# ChargerSwitch.net
KiCad netlist of a schematic drawn in Altium Designer
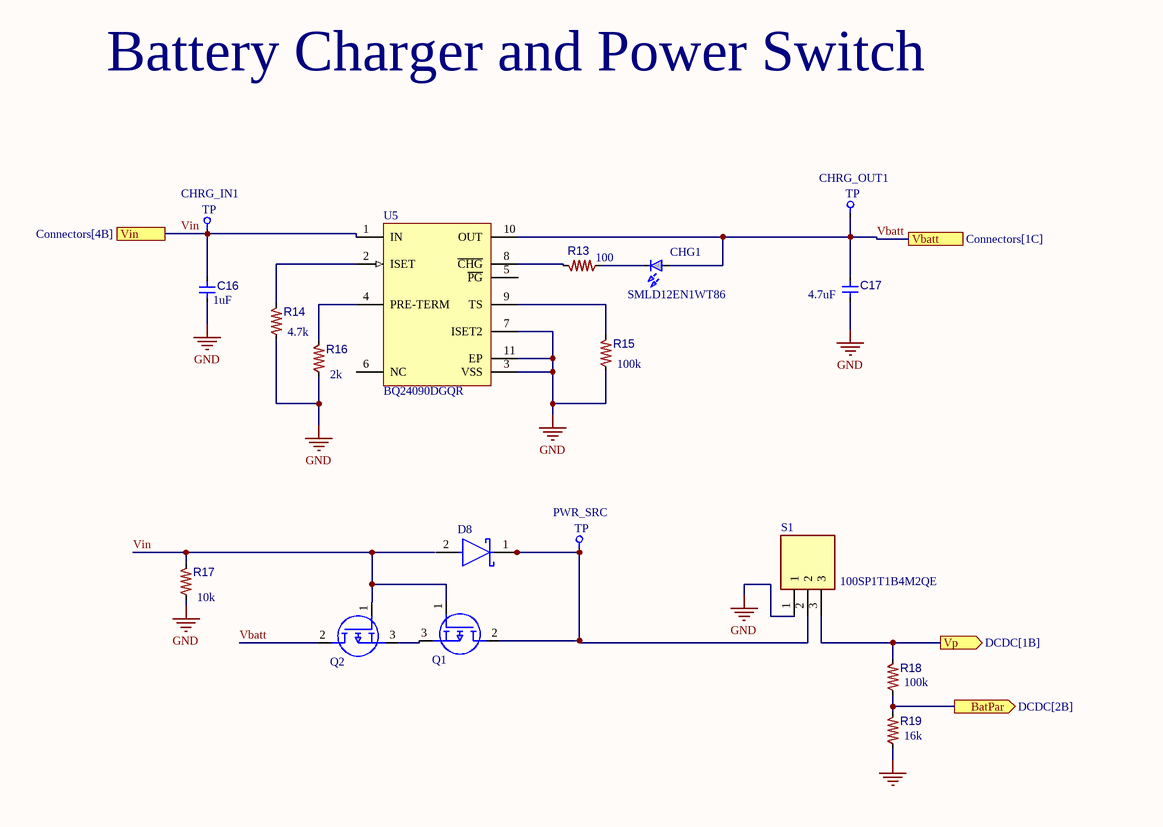
[diagram p0: ChargerSwitch.SchDoc]

(export (version "E")
  (design (tool "Eeschema 10.0.6"))
  (components
    (comp (ref "C16")
      (value "C309479")
      (footprint "New footprint 1")
      (description "6.3V 1uF X7R ±10% 0603  Multilayer Ceramic Capacitors MLCC - SMD/SMT ROHS")
      (libsource (lib "Muner") (part "CAP-NP-2"))
    )
    (comp (ref "C17")
      (value "C77045")
      (footprint "New footprint 1")
      (description "116V 4.7uF X5R ±10% 0603 Multilayer Ceramic Capacitors MLCC - SMD/SMT ROHS")
      (libsource (lib "Muner") (part "CAP-NP-2"))
    )
    (comp (ref "CHG1")
      (value "SMLD12EN1WT86")
      (footprint "LEDM168X65N")
      (description "Standard LEDs - SMD 1.6X0.8MM LOW CRNT")
      (fields (field (name "MOUSER PART NUMBER") "755-SMLD12EN1WT86"))
      (libsource (lib "Muner") (part "CMP-004-00037-6"))
    )
    (comp (ref "CHRG_IN1")
      (value "Test Pad")
      (footprint "Test Pad-Footprint-1")
      (libsource (lib "Muner") (part "Test Pad-Symbol-1"))
    )
    (comp (ref "CHRG_OUT1")
      (value "Test Pad")
      (footprint "Test Pad-Footprint-1")
      (libsource (lib "Muner") (part "Test Pad-Symbol-1"))
    )
    (comp (ref "D8")
      (value "C191986")
      (footprint "FP-MBR1020VL_R1_00001-MFG")
      (description "20V 340mV@1A 1A SOD-123F  Schottky Barrier Diodes (SBD) ROHS")
      (libsource (lib "Altium Content Vault") (part "c1678fac7984e62e0809fbf79c06691"))
    )
    (comp (ref "PWR_SRC")
      (value "Test Pad")
      (footprint "Test Pad-Footprint-1")
      (libsource (lib "Muner") (part "Test Pad-Symbol-1"))
    )
    (comp (ref "Q1")
      (value "C113491")
      (footprint "TSM260P02CXRFG")
      (description "20V 6.5A 1.4W 27mΩ@4.5V,6.5A N Channel SOT-23(TO-236)  MOSFETs ROHS")
      (fields
        (field (name "MANUFACTURER_PART_NUMBER") "TSM260P02CX RFG")
        (field (name "MOUSER PART NUMBER") "821-TSM260P02CXRFG")
      )
      (libsource (lib "Muner") (part "TSM260P02CX_RFG"))
    )
    (comp (ref "Q2")
      (value "C113491")
      (footprint "TSM260P02CXRFG")
      (description "20V 6.5A 1.4W 27mΩ@4.5V,6.5A N Channel SOT-23(TO-236)  MOSFETs ROHS")
      (fields
        (field (name "MANUFACTURER_PART_NUMBER") "TSM260P02CX RFG")
        (field (name "MOUSER PART NUMBER") "821-TSM260P02CXRFG")
      )
      (libsource (lib "Muner") (part "TSM260P02CX_RFG"))
    )
    (comp (ref "R13")
      (value "C176127")
      (footprint "0603 resistor-Footprint-1")
      (description "100mW Thick Film Resistors ±100ppm/℃ ±1% 100Ω 0603 Chip Resistor - Surface Mount ROHS")
      (libsource (lib "Muner") (part "RES-2"))
    )
    (comp (ref "R14")
      (value "C116693")
      (footprint "0603 resistor-Footprint-1")
      (description "100mW ±100ppm/℃ ±1% 4.7kΩ 0603 Chip Resistor - Surface Mount ROHS")
      (libsource (lib "Muner") (part "RES-2"))
    )
    (comp (ref "R15")
      (value "C153133")
      (footprint "0603 resistor-Footprint-1")
      (description "100mW Thick Film Resistors ±5% ±200ppm/℃ 100kΩ 0603 Chip Resistor - Surface Mount ROHS")
      (libsource (lib "Muner") (part "RES-2"))
    )
    (comp (ref "R16")
      (value "C105576")
      (footprint "0603 resistor-Footprint-1")
      (description "100mW Thick Film Resistors ±100ppm/℃ ±1% 2kΩ 0603 Chip Resistor - Surface Mount ROHS")
      (libsource (lib "Muner") (part "RES-2"))
    )
    (comp (ref "R17")
      (value "C103210")
      (footprint "0603 resistor-Footprint-1")
      (description "100mW Thick Film Resistors ±100ppm/℃ ±5% 10kΩ 0603 Chip Resistor - Surface Mount ROHS")
      (libsource (lib "Muner") (part "RES-2"))
    )
    (comp (ref "R18")
      (value "C153133")
      (footprint "0603 resistor-Footprint-1")
      (description "100mW Thick Film Resistors ±5% ±200ppm/℃ 100kΩ 0603 Chip Resistor - Surface Mount ROHS")
      (libsource (lib "Muner") (part "RES-2"))
    )
    (comp (ref "R19")
      (value "C153133")
      (footprint "0603 resistor-Footprint-1")
      (description "100mW Thick Film Resistors ±5% ±200ppm/℃ 100kΩ 0603 Chip Resistor - Surface Mount ROHS")
      (libsource (lib "Muner") (part "RES-2"))
    )
    (comp (ref "S1")
      (value "100SP1T1B4M2QE")
      (footprint "100SP1T1B4M2QE")
      (description "E-SWITCH - 100SP1T1B4M2QE - SWITCH")
      (fields (field (name "MOUSER PART NUMBER") "612-100-A1421"))
      (libsource (lib "Muner") (part "100SP1T1B4M2QE"))
    )
    (comp (ref "U5")
      (value "BQ24090DGQR")
      (footprint "DGQ0010D_L")
      (description "6.45V 锂离子/Polymer 1 1A MSOP-10-EP  Battery Management ICs ROHS")
      (fields (field (name "MANUFACTURER") "Texas Instruments"))
      (libsource (lib "Altium Content Vault") (part "TI-BQ24090DGQ10-1675X1445TP"))
    )
  )
  (nets
    (net (code "1") (name "/BatPar") (class "Default")
      (node (ref "R18") (pin "2") (pinfunction "2_2") (pintype "passive"))
      (node (ref "R19") (pin "1") (pinfunction "1_1") (pintype "passive"))
    )
    (net (code "2") (name "/Vbatt") (class "Default")
      (node (ref "C17") (pin "2") (pinfunction "2_2") (pintype "passive"))
      (node (ref "CHG1") (pin "2") (pinfunction "A_2") (pintype "passive"))
      (node (ref "CHRG_OUT1") (pin "1") (pinfunction "1_1") (pintype "passive"))
      (node (ref "Q2") (pin "2") (pinfunction "D_2") (pintype "passive"))
      (node (ref "U5") (pin "10") (pinfunction "OUT_10") (pintype "power_in"))
    )
    (net (code "3") (name "/Vin") (class "Default")
      (node (ref "C16") (pin "2") (pinfunction "2_2") (pintype "passive"))
      (node (ref "CHRG_IN1") (pin "1") (pinfunction "1_1") (pintype "passive"))
      (node (ref "Q1") (pin "1") (pinfunction "G_1") (pintype "passive"))
      (node (ref "Q2") (pin "1") (pinfunction "G_1") (pintype "passive"))
      (node (ref "R17") (pin "1") (pinfunction "1_1") (pintype "passive"))
      (node (ref "U5") (pin "1") (pinfunction "IN_1") (pintype "power_in"))
    )
    (net (code "4") (name "/Vp") (class "Default")
      (node (ref "R18") (pin "1") (pinfunction "1_1") (pintype "passive"))
      (node (ref "S1") (pin "3") (pinfunction "3_3") (pintype "passive"))
    )
    (net (code "5") (name "GND") (class "Default")
      (node (ref "C16") (pin "1") (pinfunction "1_1") (pintype "passive"))
      (node (ref "C17") (pin "1") (pinfunction "1_1") (pintype "passive"))
      (node (ref "R14") (pin "2") (pinfunction "2_2") (pintype "passive"))
      (node (ref "R15") (pin "2") (pinfunction "2_2") (pintype "passive"))
      (node (ref "R16") (pin "2") (pinfunction "2_2") (pintype "passive"))
      (node (ref "R17") (pin "2") (pinfunction "2_2") (pintype "passive"))
      (node (ref "R19") (pin "2") (pinfunction "2_2") (pintype "passive"))
      (node (ref "S1") (pin "1") (pinfunction "1_1") (pintype "passive"))
      (node (ref "U5") (pin "11") (pinfunction "EP_11") (pintype "power_in"))
      (node (ref "U5") (pin "3") (pinfunction "VSS_3") (pintype "power_in"))
      (node (ref "U5") (pin "7") (pinfunction "ISET2_7") (pintype "passive"))
    )
    (net (code "6") (name "Net-(CHG1-K)") (class "Default")
      (node (ref "CHG1") (pin "1") (pinfunction "K_1") (pintype "passive"))
      (node (ref "R13") (pin "2") (pinfunction "2_2") (pintype "passive"))
    )
    (net (code "7") (name "Net-(D8-C)") (class "Default")
      (node (ref "D8") (pin "1") (pinfunction "C_1") (pintype "passive"))
      (node (ref "PWR_SRC") (pin "1") (pinfunction "1_1") (pintype "passive"))
      (node (ref "Q1") (pin "2") (pinfunction "D_2") (pintype "passive"))
      (node (ref "S1") (pin "2") (pinfunction "2_2") (pintype "passive"))
    )
    (net (code "8") (name "Net-(Q1-S)") (class "Default")
      (node (ref "Q1") (pin "3") (pinfunction "S_3") (pintype "passive"))
      (node (ref "Q2") (pin "3") (pinfunction "S_3") (pintype "passive"))
    )
    (net (code "9") (name "Net-(U5-ISET)") (class "Default")
      (node (ref "R14") (pin "1") (pinfunction "1_1") (pintype "passive"))
      (node (ref "U5") (pin "2") (pinfunction "ISET_2") (pintype "input"))
    )
    (net (code "10") (name "Net-(U5-PRE-TERM)") (class "Default")
      (node (ref "R16") (pin "1") (pinfunction "1_1") (pintype "passive"))
      (node (ref "U5") (pin "4") (pinfunction "PRE-TERM_4") (pintype "passive"))
    )
    (net (code "11") (name "Net-(U5-TS)") (class "Default")
      (node (ref "R15") (pin "1") (pinfunction "1_1") (pintype "passive"))
      (node (ref "U5") (pin "9") (pinfunction "TS_9") (pintype "passive"))
    )
    (net (code "12") (name "Net-(U5-~{CHG})") (class "Default")
      (node (ref "R13") (pin "1") (pinfunction "1_1") (pintype "passive"))
      (node (ref "U5") (pin "8") (pinfunction "~{CHG}_8") (pintype "tri_state"))
    )
    (net (code "13") (name "unconnected-(D8-A-Pad2)") (class "Default")
      (node (ref "D8") (pin "2") (pinfunction "A_2") (pintype "passive"))
    )
    (net (code "14") (name "unconnected-(U5-NC-Pad6)") (class "Default")
      (node (ref "U5") (pin "6") (pinfunction "NC_6") (pintype "passive"))
    )
    (net (code "15") (name "unconnected-(U5-~{PG}-Pad5)") (class "Default")
      (node (ref "U5") (pin "5") (pinfunction "~{PG}_5") (pintype "tri_state"))
    )
  )
)
